# SMPS.net
KiCad netlist of a schematic drawn in Altium Designer
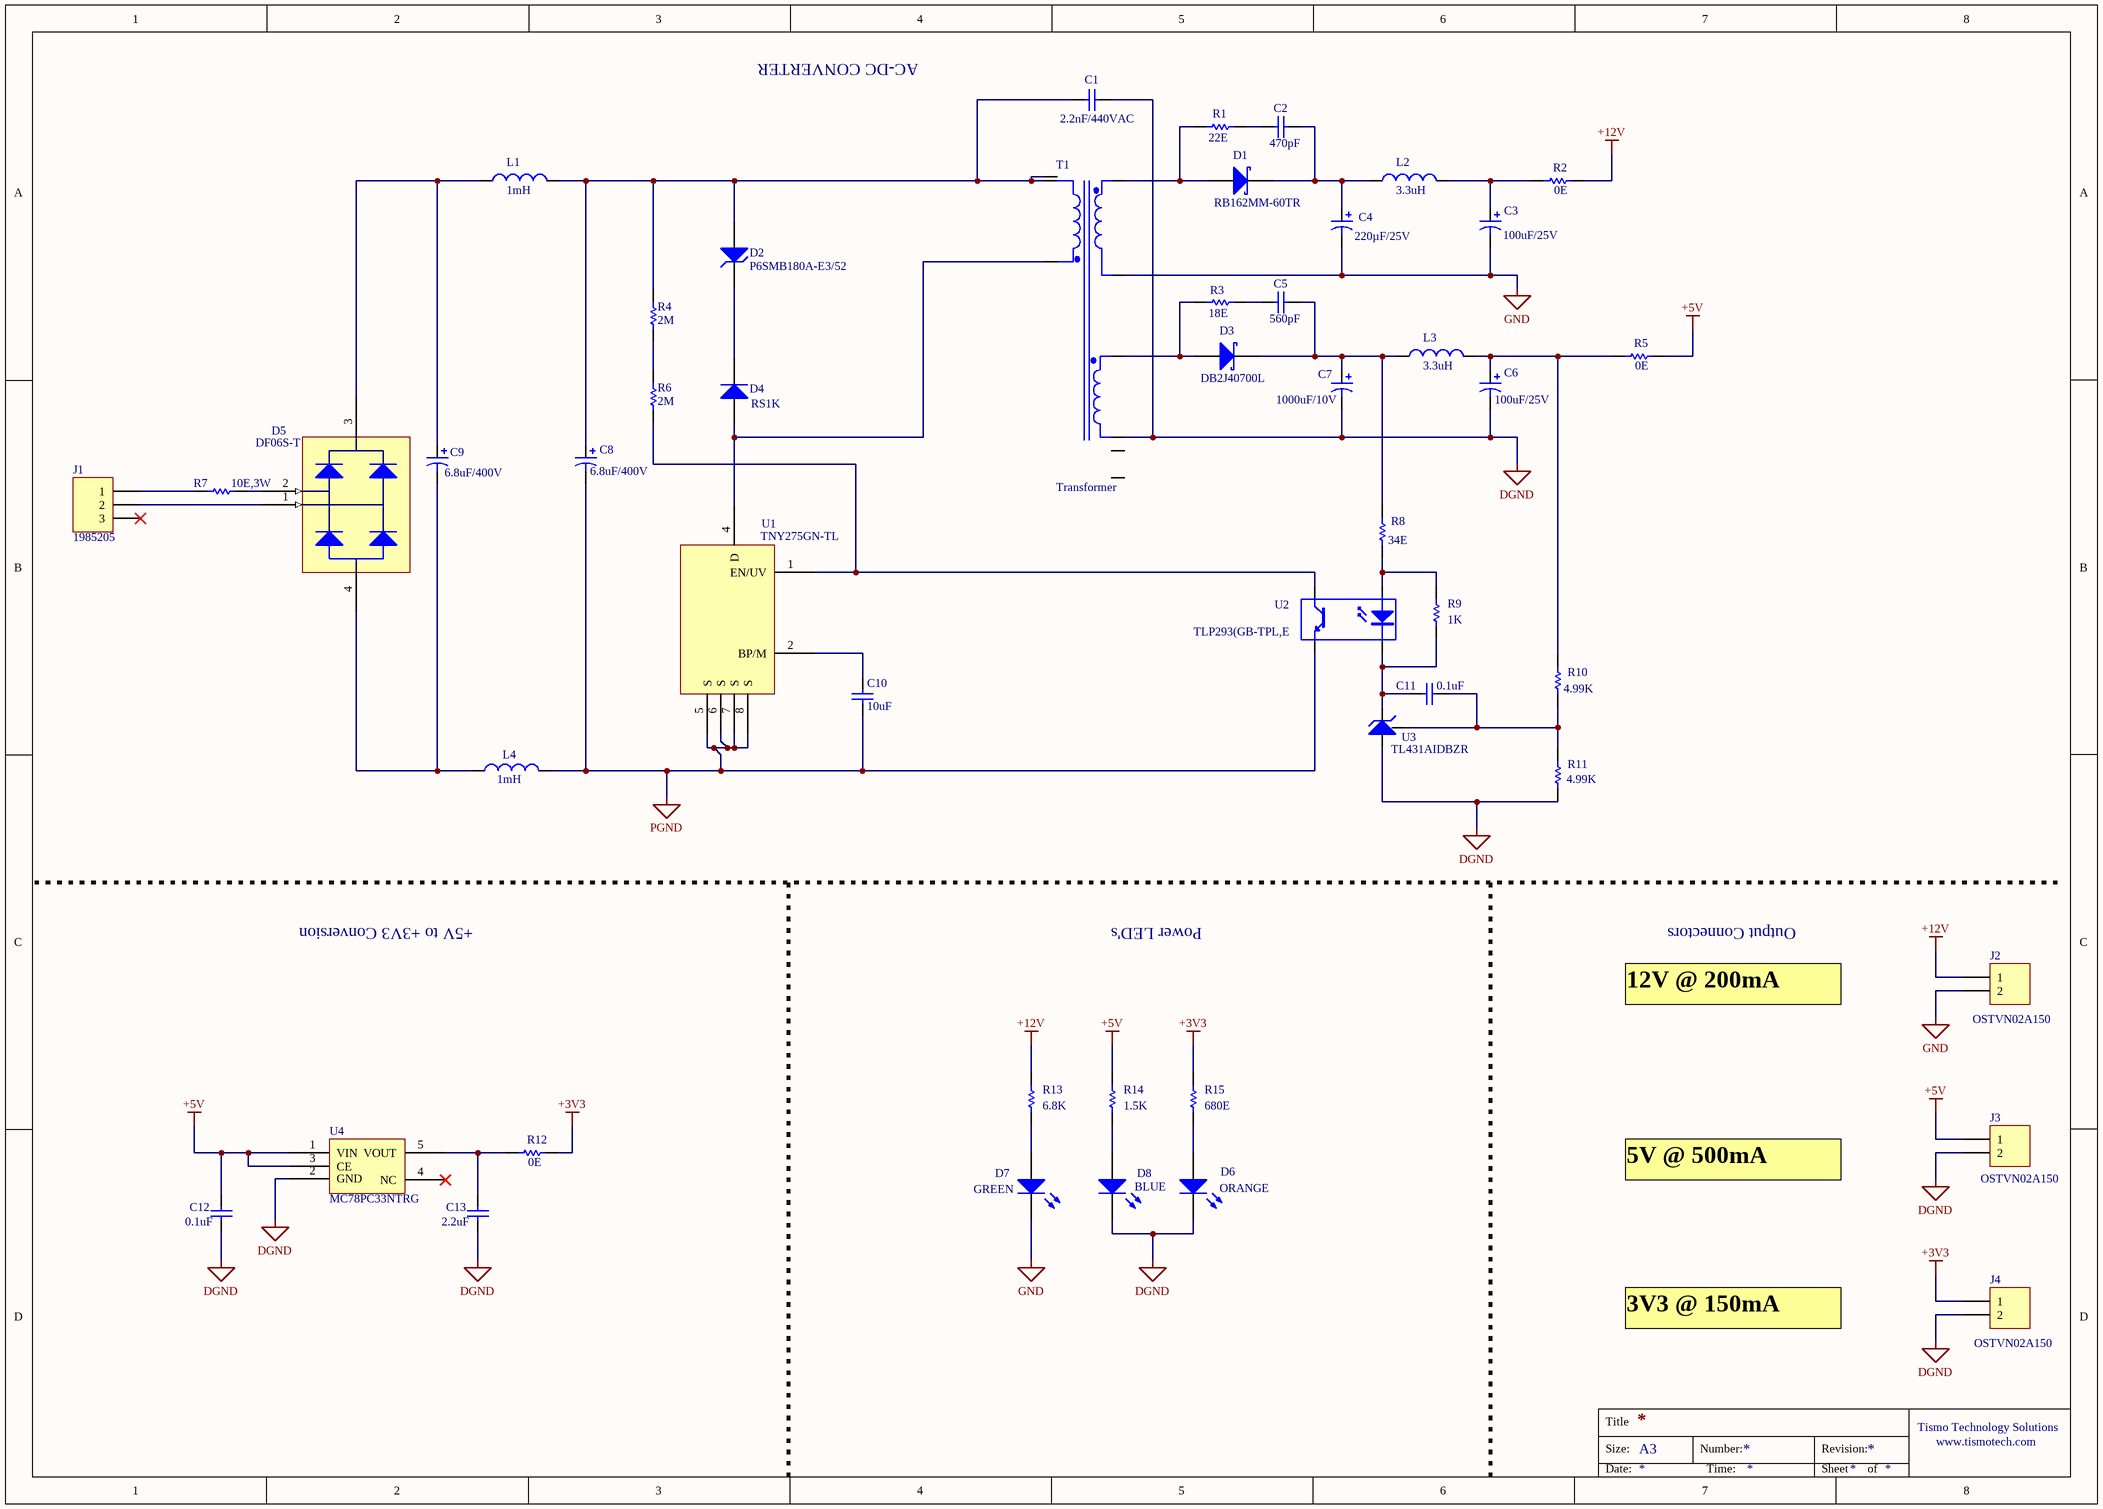
[diagram p0: SMPS.SchDoc]

(export (version "E")
  (design (tool "Eeschema 10.0.6"))
  (components
    (comp (ref "C1")
      (value "2.2nF/440VAC")
      (footprint "2.2nF CAP")
      (description "CAP CER 2200PF 440VAC Y5U RADIAL")
      (fields
        (field (name "MANUFACTURER") "Vishay BC Components")
        (field (name "MANUFACTURER PART NUMBER") "VY2222M35Y5US63V0")
      )
      (libsource (lib "Miscellaneous Devices") (part "Cap"))
    )
    (comp (ref "C2")
      (value "470pF")
      (footprint "C0603")
      (description "CAP CER 470PF 100V C0G/NP0 0603")
      (fields
        (field (name "MANUFACTURER") "Murata Electronics North America")
        (field (name "MANUFACTURER PART NUMBER") "GCM1885C2A471JA16D")
      )
      (libsource (lib "Miscellaneous Devices") (part "Cap"))
    )
    (comp (ref "C3")
      (value "100uF/25V")
      (footprint "CAP 6.3MM DIA")
      (description "CAP ALUM 100UF 20% 25V RADIAL")
      (fields
        (field (name "MANUFACTURER") "United Chemi-Con")
        (field (name "MANUFACTURER PART NUMBER") "ELXZ250ELL101MFB5D")
      )
      (libsource (lib "Miscellaneous Devices") (part "Cap Pol2"))
    )
    (comp (ref "C4")
      (value "220µF/25V")
      (footprint "CAP 8 MM DIA")
      (description "CAP ALUM 220UF 20% 25V RADIAL")
      (fields
        (field (name "MANUFACTURER") "United Chemi-Con")
        (field (name "MANUFACTURER PART NUMBER") "EKZE250ELL221MHB5D")
      )
      (libsource (lib "Miscellaneous Devices") (part "Cap Pol2"))
    )
    (comp (ref "C5")
      (value "560pF")
      (footprint "C0603")
      (description "CAP CER 560PF 100V C0G/NP0 0603")
      (fields
        (field (name "MANUFACTURER") "Murata Electronics North America")
        (field (name "MANUFACTURER PART NUMBER") "GCM1885C2A561JA16D")
      )
      (libsource (lib "Miscellaneous Devices") (part "Cap"))
    )
    (comp (ref "C6")
      (value "100uF/25V")
      (footprint "CAP 6.3MM DIA")
      (description "CAP ALUM 100UF 20% 25V RADIAL")
      (fields
        (field (name "MANUFACTURER") "United Chemi-Con")
        (field (name "MANUFACTURER PART NUMBER") "ELXZ250ELL101MFB5D")
      )
      (libsource (lib "Miscellaneous Devices") (part "Cap Pol2"))
    )
    (comp (ref "C7")
      (value "1000uF/10V")
      (footprint "CAP 10MM DIA")
      (description "CAP ALUM 1000UF 20% 10V RADIAL")
      (fields
        (field (name "MANUFACTURER") "Wurth Electronics Inc.")
        (field (name "MANUFACTURER PART NUMBER") "860020275015")
      )
      (libsource (lib "Miscellaneous Devices") (part "Cap Pol2"))
    )
    (comp (ref "C8")
      (value "6.8uF/400V")
      (footprint "CAP 8 MM DIA")
      (description "CAP ALUM 6.8UF 20% 400V RADIAL")
      (fields
        (field (name "MANUFACTURER") "Wurth Electronics Inc.")
        (field (name "MANUFACTURER PART NUMBER") "860021374009")
      )
      (libsource (lib "Miscellaneous Devices") (part "Cap Pol2"))
    )
    (comp (ref "C9")
      (value "6.8uF/400V")
      (footprint "CAP 8 MM DIA")
      (description "CAP ALUM 6.8UF 20% 400V RADIAL")
      (fields
        (field (name "MANUFACTURER") "Wurth Electronics Inc.")
        (field (name "MANUFACTURER PART NUMBER") "860021374009")
      )
      (libsource (lib "Miscellaneous Devices") (part "Cap Pol2"))
    )
    (comp (ref "C10")
      (value "10uF")
      (footprint "R0805_2012")
      (description "CAP CER 10UF 16V X7R 1206")
      (fields
        (field (name "MANUFACTURER") "TDK Corporation")
        (field (name "MANUFACTURER PART NUMBER") "C3216X7R1C106K160AC")
      )
      (libsource (lib "Miscellaneous Devices") (part "Cap"))
    )
    (comp (ref "C11")
      (value "0.1uF")
      (footprint "R0805_2012")
      (description "CAP CER 0.1UF 16V X7R 0402")
      (fields
        (field (name "MANUFACTURER") "TDK Corporation")
        (field (name "MANUFACTURER PART NUMBER") "C1005X7R1C104K050BC")
      )
      (libsource (lib "Miscellaneous Devices") (part "Cap"))
    )
    (comp (ref "C12")
      (value "0.1uF")
      (footprint "R0805_2012")
      (description "CAP CER 0.1UF 16V X7R 0402")
      (fields
        (field (name "MANUFACTURER") "TDK Corporation")
        (field (name "MANUFACTURER PART NUMBER") "C1005X7R1C104K050BC")
      )
      (libsource (lib "Miscellaneous Devices") (part "Cap"))
    )
    (comp (ref "C13")
      (value "2.2uF")
      (footprint "R0805_2012")
      (description "CAP CER 2.2UF 50V X5R 0603")
      (fields
        (field (name "MANUFACTURER") "Murata Electronics North America")
        (field (name "MANUFACTURER PART NUMBER") "GRM188R61H225KE11D")
      )
      (libsource (lib "Miscellaneous Devices") (part "Cap"))
    )
    (comp (ref "D1")
      (value "RB162MM-60TR")
      (footprint "GS-1_A")
      (description "DIODE SCHOTTKY 60V 1A PMDU")
      (fields (field (name "MANUFACTURER") "Rohm Semiconductor"))
      (libsource (lib "Miscellaneous Devices") (part "Diode BAT17"))
    )
    (comp (ref "D2")
      (value "P6SMB180A-E3/52")
      (footprint "P6SMB")
      (description "TVS DIODE 154VWM 246VC SMB")
      (fields (field (name "MANUFACTURER") "Vishay Semiconductor Diodes Division"))
      (libsource (lib "Miscellaneous Devices") (part "D Zener"))
    )
    (comp (ref "D3")
      (value "DB2J40700L")
      (footprint "SOD323")
      (description "DIODE SCHOTTKY 40V 500MA SMINI2")
      (fields (field (name "MANUFACTURER") "Panasonic Electronic Components"))
      (libsource (lib "Miscellaneous Devices") (part "Diode BAT17"))
    )
    (comp (ref "D4")
      (value "RS1K")
      (footprint "SMA")
      (description "DIODE GEN PURP 800V 1A SMA")
      (fields (field (name "MANUFACTURER") "Fairchild Semiconductor"))
      (libsource (lib "Miscellaneous Devices") (part "Diode"))
    )
    (comp (ref "D5")
      (value "DF06S-T")
      (footprint "DF06S")
      (description "RECT BRIDGE GPP 1A 600V DFS")
      (fields (field (name "MANUFACTURER") "Diodes Incorporated"))
      (libsource (lib "PoC2_1") (part "BRIDGE RECTIFIER"))
    )
    (comp (ref "D6")
      (value "ORANGE")
      (footprint "1.6X0.8X0.8")
      (description "LED ORANGE CLEAR 0603 SMD")
      (fields
        (field (name "MANUFACTURER") "Lite-On Inc.")
        (field (name "MANUFACTURER PART NUMBER") "LTST-C190KFKT")
      )
      (libsource (lib "Miscellaneous Devices") (part "LED0"))
    )
    (comp (ref "D7")
      (value "GREEN")
      (footprint "1.6X0.8X0.8")
      (description "LED GREEN CLEAR 0603 SMD")
      (fields
        (field (name "MANUFACTURER") "Lite-On Inc.")
        (field (name "MANUFACTURER PART NUMBER") "LTST-C190KGKT")
      )
      (libsource (lib "Miscellaneous Devices") (part "LED0"))
    )
    (comp (ref "D8")
      (value "BLUE")
      (footprint "1.6X0.8X0.8")
      (description "LED BLUE CLEAR 0603 SMD")
      (fields
        (field (name "MANUFACTURER") "Lite-On Inc.")
        (field (name "MANUFACTURER PART NUMBER") "LTST-C193TBKT-5A")
      )
      (libsource (lib "Miscellaneous Devices") (part "LED0"))
    )
    (comp (ref "J1")
      (value "1985205")
      (footprint "AC SUPPLY CONNECTOR")
      (description "TERM BLOCK PCB 3POS 3.5MM GREEN")
      (fields (field (name "MANUFACTURER") "Phoenix Contact"))
      (libsource (lib "Miscellaneous Connectors") (part "Header 3"))
    )
    (comp (ref "J2")
      (value "OSTVN02A150")
      (footprint "OSTVN02A150")
      (description "CONN TERM BLOCK 2.54MM 2POS PCB")
      (fields (field (name "MANUFACTURER") "On Shore Technology Inc."))
      (libsource (lib "Miscellaneous Connectors") (part "Header 2"))
    )
    (comp (ref "J3")
      (value "OSTVN02A150")
      (footprint "OSTVN02A150")
      (description "CONN TERM BLOCK 2.54MM 2POS PCB")
      (fields (field (name "MANUFACTURER") "On Shore Technology Inc."))
      (libsource (lib "Miscellaneous Connectors") (part "Header 2"))
    )
    (comp (ref "J4")
      (value "OSTVN02A150")
      (footprint "OSTVN02A150")
      (description "CONN TERM BLOCK 2.54MM 2POS PCB")
      (fields (field (name "MANUFACTURER") "On Shore Technology Inc."))
      (libsource (lib "Miscellaneous Connectors") (part "Header 2"))
    )
    (comp (ref "L1")
      (value "1mH")
      (footprint "SDR0805-102KL")
      (description "FIXED IND 1MH 210MA 4.5 OHM SMD")
      (fields
        (field (name "MANUFACTURER") "Bourns Inc.")
        (field (name "MANUFACTURER PART NUMBER") "SDR0805-102KL")
      )
      (libsource (lib "Miscellaneous Devices") (part "Inductor"))
    )
    (comp (ref "L2")
      (value "3.3uH")
      (footprint "SDE0604A-120M")
      (description "FIXED IND 3.3UH 3.8A 60 MOHM SMD")
      (fields
        (field (name "MANUFACTURER") "Bourns Inc.")
        (field (name "MANUFACTURER PART NUMBER") "SDE0604A-3R3M")
      )
      (libsource (lib "Miscellaneous Devices") (part "Inductor"))
    )
    (comp (ref "L3")
      (value "3.3uH")
      (footprint "SDE0604A-120M")
      (description "FIXED IND 3.3UH 3.8A 60 MOHM SMD")
      (fields
        (field (name "MANUFACTURER") "Bourns Inc.")
        (field (name "MANUFACTURER PART NUMBER") "SDE0604A-3R3M")
      )
      (libsource (lib "Miscellaneous Devices") (part "Inductor"))
    )
    (comp (ref "L4")
      (value "1mH")
      (footprint "SDR0805-102KL")
      (description "FIXED IND 1MH 210MA 4.5 OHM SMD")
      (fields
        (field (name "MANUFACTURER") "Bourns Inc.")
        (field (name "MANUFACTURER PART NUMBER") "SDR0805-102KL")
      )
      (libsource (lib "Miscellaneous Devices") (part "Inductor"))
    )
    (comp (ref "R1")
      (value "22E")
      (footprint "1206")
      (description "RES SMD 22 OHM 5% 1/4W 1206")
      (fields
        (field (name "MANUFACTURER") "Panasonic Electronic Components")
        (field (name "MANUFACTURER PART NUMBER") "ERJ-8GEYJ220V")
      )
      (libsource (lib "Miscellaneous Devices") (part "Res1"))
    )
    (comp (ref "R2")
      (value "0E")
      (footprint "R0603")
      (description "RES SMD 0.0OHM JUMPER 1/10W 0603")
      (fields
        (field (name "MANUFACTURER") "Yageo")
        (field (name "MANUFACTURER PART NUMBER") "RC0603JR-070RL")
      )
      (libsource (lib "Miscellaneous Devices") (part "Res1"))
    )
    (comp (ref "R3")
      (value "18E")
      (footprint "1206")
      (description "RES SMD 18 OHM 1% 1/4W 1206")
      (fields
        (field (name "MANUFACTURER") "Panasonic Electronic Components")
        (field (name "MANUFACTURER PART NUMBER") "ERJ-8ENF18R0V")
      )
      (libsource (lib "Miscellaneous Devices") (part "Res1"))
    )
    (comp (ref "R4")
      (value "2M")
      (footprint "R1206 - Small pad")
      (description "RES SMD 2M OHM 5% 1/4W 1206")
      (fields
        (field (name "MANUFACTURER") "Yageo")
        (field (name "MANUFACTURER PART NUMBER") "RC1206JR-072ML")
      )
      (libsource (lib "Miscellaneous Devices") (part "Res1"))
    )
    (comp (ref "R5")
      (value "0E")
      (footprint "R0603")
      (description "RES SMD 0.0OHM JUMPER 1/10W 0603")
      (fields
        (field (name "MANUFACTURER") "Yageo")
        (field (name "MANUFACTURER PART NUMBER") "RC0603JR-070RL")
      )
      (libsource (lib "Miscellaneous Devices") (part "Res1"))
    )
    (comp (ref "R6")
      (value "2M")
      (footprint "R1206 - Small pad")
      (description "RES SMD 2M OHM 5% 1/4W 1206")
      (fields
        (field (name "MANUFACTURER") "Yageo")
        (field (name "MANUFACTURER PART NUMBER") "RC1206JR-072ML")
      )
      (libsource (lib "Miscellaneous Devices") (part "Res1"))
    )
    (comp (ref "R7")
      (value "10E,3W")
      (footprint "FUSIBLE RESISTOR")
      (description "RES 10 OHM 3W 5% AXIAL")
      (fields
        (field (name "MANUFACTURER") "Yageo")
        (field (name "MANUFACTURER PART NUMBER") "FKN3WSJT-73-10R")
      )
      (libsource (lib "Miscellaneous Devices") (part "Res1"))
    )
    (comp (ref "R8")
      (value "34E")
      (footprint "R0603")
      (description "RES SMD 34 OHM 1% 1/10W 0603")
      (fields
        (field (name "MANUFACTURER") "Yageo")
        (field (name "MANUFACTURER PART NUMBER") "RC0603FR-0734RL")
      )
      (libsource (lib "Miscellaneous Devices") (part "Res1"))
    )
    (comp (ref "R9")
      (value "1K")
      (footprint "R0603")
      (description "RES SMD 1K OHM 1% 1/10W 0603")
      (fields
        (field (name "MANUFACTURER") "Yageo")
        (field (name "MANUFACTURER PART NUMBER") "RC0603FR-071KL")
      )
      (libsource (lib "Miscellaneous Devices") (part "Res1"))
    )
    (comp (ref "R10")
      (value "4.99K")
      (footprint "R0603")
      (description "RES SMD 4.99K OHM 1% 1/10W 0603")
      (fields
        (field (name "MANUFACTURER") "Yageo")
        (field (name "MANUFACTURER PART NUMBER") "RC0603FR-074K99L")
      )
      (libsource (lib "Miscellaneous Devices") (part "Res1"))
    )
    (comp (ref "R11")
      (value "4.99K")
      (footprint "R0603")
      (description "RES SMD 4.99K OHM 1% 1/10W 0603")
      (fields
        (field (name "MANUFACTURER") "Yageo")
        (field (name "MANUFACTURER PART NUMBER") "RC0603FR-074K99L")
      )
      (libsource (lib "Miscellaneous Devices") (part "Res1"))
    )
    (comp (ref "R12")
      (value "0E")
      (footprint "R0603")
      (description "RES SMD 0.0OHM JUMPER 1/10W 0603")
      (fields
        (field (name "MANUFACTURER") "Yageo")
        (field (name "MANUFACTURER PART NUMBER") "RC0603JR-070RL")
      )
      (libsource (lib "Miscellaneous Devices") (part "Res1"))
    )
    (comp (ref "R13")
      (value "6.8K")
      (footprint "R0603")
      (description "RES SMD 6.8K OHM 5% 1/10W 0603")
      (fields
        (field (name "MANUFACTURER") "Yageo")
        (field (name "MANUFACTURER PART NUMBER") "RC0603JR-076K8L")
      )
      (libsource (lib "Miscellaneous Devices") (part "Res1"))
    )
    (comp (ref "R14")
      (value "1.5K")
      (footprint "R0603")
      (description "RES SMD 1.5K OHM 5% 1/10W 0603")
      (fields
        (field (name "MANUFACTURER") "Yageo")
        (field (name "MANUFACTURER PART NUMBER") "RC0603JR-071K5L")
      )
      (libsource (lib "Miscellaneous Devices") (part "Res1"))
    )
    (comp (ref "R15")
      (value "680E")
      (footprint "R0603")
      (description "RES SMD 680 OHM 5% 1/10W 0603")
      (fields
        (field (name "MANUFACTURER") "Yageo")
        (field (name "MANUFACTURER PART NUMBER") "RC0603JR-07680RL")
      )
      (libsource (lib "Miscellaneous Devices") (part "Res1"))
    )
    (comp (ref "T1") (value "Transformer") (footprint "Tra") (libsource (lib "PoC2_1") (part "Transformer")))
    (comp (ref "U1")
      (value "TNY275GN-TL")
      (footprint "TNY284DG")
      (description "IC OFFLINE SWIT OVP OTP HV 8SMD")
      (fields (field (name "MANUFACTURER") "Power Integrations"))
      (libsource (lib "PoC2_1") (part "TNY284"))
    )
    (comp (ref "U2")
      (value "TLP293(GB-TPL,E")
      (footprint "P25S01L")
      (description "OPTOISOLATOR 3.75KV TRANS 4-SO")
      (fields (field (name "MANUFACTURER") "Toshiba Semiconductor and Storage"))
      (libsource (lib "Schlib1") (part "PS250-1"))
    )
    (comp (ref "U3")
      (value "TL431AIDBZR")
      (footprint "SOT-23_M")
      (description "IC VREF SHUNT ADJ SOT23-3")
      (fields (field (name "MANUFACTURER") "Texas Instruments") (field (name "TOLERANCE") "±1%"))
      (libsource (lib "SMPS_12V&5V Out") (part "TL431"))
    )
    (comp (ref "U4")
      (value "MC78PC33NTRG")
      (footprint "SOT23-5_N")
      (description "IC REG LINEAR 3.3V 150MA 5TSOP")
      (fields (field (name "MANUFACTURER") "ON Semiconductor"))
      (libsource (lib "SMPS_12V&5V Out") (part "MC78PC33NTRG"))
    )
  )
  (nets
    (net (code "1") (name "+3V3") (class "Default")
      (node (ref "J4") (pin "1") (pinfunction "1_1") (pintype "passive"))
      (node (ref "R12") (pin "2") (pinfunction "2_2") (pintype "passive"))
      (node (ref "R15") (pin "2") (pinfunction "2_2") (pintype "passive"))
    )
    (net (code "2") (name "+5V") (class "Default")
      (node (ref "C12") (pin "1") (pinfunction "1_1") (pintype "passive"))
      (node (ref "J3") (pin "1") (pinfunction "1_1") (pintype "passive"))
      (node (ref "R14") (pin "2") (pinfunction "2_2") (pintype "passive"))
      (node (ref "R5") (pin "2") (pinfunction "2_2") (pintype "passive"))
      (node (ref "U4") (pin "1") (pinfunction "VIN_1") (pintype "power_in"))
      (node (ref "U4") (pin "3") (pinfunction "CE_3") (pintype "passive"))
    )
    (net (code "3") (name "+12V") (class "Default")
      (node (ref "J2") (pin "1") (pinfunction "1_1") (pintype "passive"))
      (node (ref "R13") (pin "2") (pinfunction "2_2") (pintype "passive"))
      (node (ref "R2") (pin "2") (pinfunction "2_2") (pintype "passive"))
    )
    (net (code "4") (name "DGND") (class "Default")
      (node (ref "C1") (pin "2") (pinfunction "2_2") (pintype "passive"))
      (node (ref "C12") (pin "2") (pinfunction "2_2") (pintype "passive"))
      (node (ref "C13") (pin "2") (pinfunction "2_2") (pintype "passive"))
      (node (ref "C6") (pin "2") (pinfunction "2_2") (pintype "passive"))
      (node (ref "C7") (pin "2") (pinfunction "2_2") (pintype "passive"))
      (node (ref "D6") (pin "2") (pinfunction "K_2") (pintype "passive"))
      (node (ref "D8") (pin "2") (pinfunction "K_2") (pintype "passive"))
      (node (ref "J3") (pin "2") (pinfunction "2_2") (pintype "passive"))
      (node (ref "J4") (pin "2") (pinfunction "2_2") (pintype "passive"))
      (node (ref "R11") (pin "1") (pinfunction "1_1") (pintype "passive"))
      (node (ref "T1") (pin "6") (pintype "passive"))
      (node (ref "U3") (pin "3") (pinfunction "A_3") (pintype "passive"))
      (node (ref "U4") (pin "2") (pinfunction "GND_2") (pintype "power_in"))
    )
    (net (code "5") (name "GND") (class "Default")
      (node (ref "C3") (pin "2") (pinfunction "2_2") (pintype "passive"))
      (node (ref "C4") (pin "2") (pinfunction "2_2") (pintype "passive"))
      (node (ref "D7") (pin "2") (pinfunction "K_2") (pintype "passive"))
      (node (ref "J2") (pin "2") (pinfunction "2_2") (pintype "passive"))
      (node (ref "T1") (pin "9") (pintype "passive"))
    )
    (net (code "6") (name "Net-(C2-Pad1)") (class "Default")
      (node (ref "C2") (pin "1") (pinfunction "1_1") (pintype "passive"))
      (node (ref "R1") (pin "2") (pinfunction "2_2") (pintype "passive"))
    )
    (net (code "7") (name "Net-(C2-Pad2)") (class "Default")
      (node (ref "C2") (pin "2") (pinfunction "2_2") (pintype "passive"))
      (node (ref "C4") (pin "1") (pinfunction "1_1") (pintype "passive"))
      (node (ref "D1") (pin "K") (pinfunction "K_K") (pintype "passive"))
      (node (ref "L2") (pin "1") (pinfunction "1_1") (pintype "passive"))
    )
    (net (code "8") (name "Net-(C3-Pad1)") (class "Default")
      (node (ref "C3") (pin "1") (pinfunction "1_1") (pintype "passive"))
      (node (ref "L2") (pin "2") (pinfunction "2_2") (pintype "passive"))
      (node (ref "R2") (pin "1") (pinfunction "1_1") (pintype "passive"))
    )
    (net (code "9") (name "Net-(C5-Pad1)") (class "Default")
      (node (ref "C5") (pin "1") (pinfunction "1_1") (pintype "passive"))
      (node (ref "R3") (pin "2") (pinfunction "2_2") (pintype "passive"))
    )
    (net (code "10") (name "Net-(C5-Pad2)") (class "Default")
      (node (ref "C5") (pin "2") (pinfunction "2_2") (pintype "passive"))
      (node (ref "C7") (pin "1") (pinfunction "1_1") (pintype "passive"))
      (node (ref "D3") (pin "K") (pinfunction "K_K") (pintype "passive"))
      (node (ref "L3") (pin "1") (pinfunction "1_1") (pintype "passive"))
      (node (ref "R8") (pin "2") (pinfunction "2_2") (pintype "passive"))
    )
    (net (code "11") (name "Net-(C6-Pad1)") (class "Default")
      (node (ref "C6") (pin "1") (pinfunction "1_1") (pintype "passive"))
      (node (ref "L3") (pin "2") (pinfunction "2_2") (pintype "passive"))
      (node (ref "R10") (pin "2") (pinfunction "2_2") (pintype "passive"))
      (node (ref "R5") (pin "1") (pinfunction "1_1") (pintype "passive"))
    )
    (net (code "12") (name "Net-(C9-Pad1)") (class "Default")
      (node (ref "C9") (pin "1") (pinfunction "1_1") (pintype "passive"))
      (node (ref "D5") (pin "3") (pintype "passive"))
      (node (ref "L1") (pin "1") (pinfunction "1_1") (pintype "passive"))
    )
    (net (code "13") (name "Net-(C9-Pad2)") (class "Default")
      (node (ref "C9") (pin "2") (pinfunction "2_2") (pintype "passive"))
      (node (ref "D5") (pin "4") (pintype "passive"))
      (node (ref "L4") (pin "1") (pinfunction "1_1") (pintype "passive"))
    )
    (net (code "14") (name "Net-(C11-Pad1)") (class "Default")
      (node (ref "C11") (pin "1") (pinfunction "1_1") (pintype "passive"))
      (node (ref "R10") (pin "1") (pinfunction "1_1") (pintype "passive"))
      (node (ref "R11") (pin "2") (pinfunction "2_2") (pintype "passive"))
      (node (ref "U3") (pin "1") (pintype "passive"))
    )
    (net (code "15") (name "Net-(D1-PadA)") (class "Default")
      (node (ref "D1") (pin "A") (pinfunction "A_A") (pintype "passive"))
      (node (ref "R1") (pin "1") (pinfunction "1_1") (pintype "passive"))
      (node (ref "T1") (pin "10") (pintype "passive"))
    )
    (net (code "16") (name "Net-(D2-A)") (class "Default")
      (node (ref "C1") (pin "1") (pinfunction "1_1") (pintype "passive"))
      (node (ref "C8") (pin "1") (pinfunction "1_1") (pintype "passive"))
      (node (ref "D2") (pin "1") (pinfunction "A_1") (pintype "passive"))
      (node (ref "L1") (pin "2") (pinfunction "2_2") (pintype "passive"))
      (node (ref "R4") (pin "2") (pinfunction "2_2") (pintype "passive"))
      (node (ref "T1") (pin "1") (pintype "passive"))
      (node (ref "T1") (pin "2") (pintype "passive"))
    )
    (net (code "17") (name "Net-(D2-K)") (class "Default")
      (node (ref "D2") (pin "2") (pinfunction "K_2") (pintype "passive"))
      (node (ref "D4") (pin "2") (pinfunction "K_2") (pintype "passive"))
    )
    (net (code "18") (name "Net-(D3-PadA)") (class "Default")
      (node (ref "D3") (pin "A") (pinfunction "A_A") (pintype "passive"))
      (node (ref "R3") (pin "1") (pinfunction "1_1") (pintype "passive"))
      (node (ref "T1") (pin "7") (pintype "passive"))
    )
    (net (code "19") (name "Net-(D4-A)") (class "Default")
      (node (ref "D4") (pin "1") (pinfunction "A_1") (pintype "passive"))
      (node (ref "T1") (pin "4") (pintype "passive"))
      (node (ref "U1") (pin "4") (pinfunction "D_4") (pintype "passive"))
    )
    (net (code "20") (name "Net-(D5-Pad1)") (class "Default")
      (node (ref "D5") (pin "1") (pintype "input"))
      (node (ref "J1") (pin "2") (pinfunction "2_2") (pintype "passive"))
    )
    (net (code "21") (name "Net-(D5-Pad2)") (class "Default")
      (node (ref "D5") (pin "2") (pintype "input"))
      (node (ref "R7") (pin "2") (pinfunction "2_2") (pintype "passive"))
    )
    (net (code "22") (name "Net-(D6-A)") (class "Default")
      (node (ref "D6") (pin "1") (pinfunction "A_1") (pintype "passive"))
      (node (ref "R15") (pin "1") (pinfunction "1_1") (pintype "passive"))
    )
    (net (code "23") (name "Net-(D7-A)") (class "Default")
      (node (ref "D7") (pin "1") (pinfunction "A_1") (pintype "passive"))
      (node (ref "R13") (pin "1") (pinfunction "1_1") (pintype "passive"))
    )
    (net (code "24") (name "Net-(D8-A)") (class "Default")
      (node (ref "D8") (pin "1") (pinfunction "A_1") (pintype "passive"))
      (node (ref "R14") (pin "1") (pinfunction "1_1") (pintype "passive"))
    )
    (net (code "25") (name "Net-(J1-Pad1)") (class "Default")
      (node (ref "J1") (pin "1") (pinfunction "1_1") (pintype "passive"))
      (node (ref "R7") (pin "1") (pinfunction "1_1") (pintype "passive"))
    )
    (net (code "26") (name "Net-(R4-Pad1)") (class "Default")
      (node (ref "R4") (pin "1") (pinfunction "1_1") (pintype "passive"))
      (node (ref "R6") (pin "2") (pinfunction "2_2") (pintype "passive"))
    )
    (net (code "27") (name "Net-(U1-BP{slash}M)") (class "Default")
      (node (ref "C10") (pin "1") (pinfunction "1_1") (pintype "passive"))
      (node (ref "U1") (pin "2") (pinfunction "BP/M_2") (pintype "passive"))
    )
    (net (code "28") (name "Net-(U1-EN{slash}UV)") (class "Default")
      (node (ref "R6") (pin "1") (pinfunction "1_1") (pintype "passive"))
      (node (ref "U1") (pin "1") (pinfunction "EN/UV_1") (pintype "passive"))
      (node (ref "U2") (pin "4") (pinfunction "C_4") (pintype "passive"))
    )
    (net (code "29") (name "Net-(U2-A)") (class "Default")
      (node (ref "R8") (pin "1") (pinfunction "1_1") (pintype "passive"))
      (node (ref "R9") (pin "2") (pinfunction "2_2") (pintype "passive"))
      (node (ref "U2") (pin "1") (pinfunction "A_1") (pintype "passive"))
    )
    (net (code "30") (name "Net-(U2-K)") (class "Default")
      (node (ref "C11") (pin "2") (pinfunction "2_2") (pintype "passive"))
      (node (ref "R9") (pin "1") (pinfunction "1_1") (pintype "passive"))
      (node (ref "U2") (pin "2") (pinfunction "K_2") (pintype "passive"))
      (node (ref "U3") (pin "2") (pinfunction "K_2") (pintype "passive"))
    )
    (net (code "31") (name "Net-(U4-VOUT)") (class "Default")
      (node (ref "C13") (pin "1") (pinfunction "1_1") (pintype "passive"))
      (node (ref "R12") (pin "1") (pinfunction "1_1") (pintype "passive"))
      (node (ref "U4") (pin "5") (pinfunction "VOUT_5") (pintype "passive"))
    )
    (net (code "32") (name "PGND") (class "Default")
      (node (ref "C10") (pin "2") (pinfunction "2_2") (pintype "passive"))
      (node (ref "C8") (pin "2") (pinfunction "2_2") (pintype "passive"))
      (node (ref "L4") (pin "2") (pinfunction "2_2") (pintype "passive"))
      (node (ref "U1") (pin "5") (pinfunction "S_5") (pintype "passive"))
      (node (ref "U1") (pin "6") (pinfunction "S_6") (pintype "passive"))
      (node (ref "U1") (pin "7") (pinfunction "S_7") (pintype "passive"))
      (node (ref "U1") (pin "8") (pinfunction "S_8") (pintype "passive"))
      (node (ref "U2") (pin "3") (pinfunction "E_3") (pintype "passive"))
    )
    (net (code "33") (name "unconnected-(J1-Pad3)") (class "Default")
      (node (ref "J1") (pin "3") (pinfunction "3_3") (pintype "passive+no_connect"))
    )
    (net (code "34") (name "unconnected-(T1-Pad3)") (class "Default")
      (node (ref "T1") (pin "3") (pintype "passive"))
    )
    (net (code "35") (name "unconnected-(T1-Pad5)") (class "Default")
      (node (ref "T1") (pin "5") (pintype "passive"))
    )
    (net (code "36") (name "unconnected-(U4-NC-Pad4)") (class "Default")
      (node (ref "U4") (pin "4") (pinfunction "NC_4") (pintype "passive+no_connect"))
    )
  )
)
